# hm3_redraw.net
KiCad netlist of a schematic drawn in EAGLE
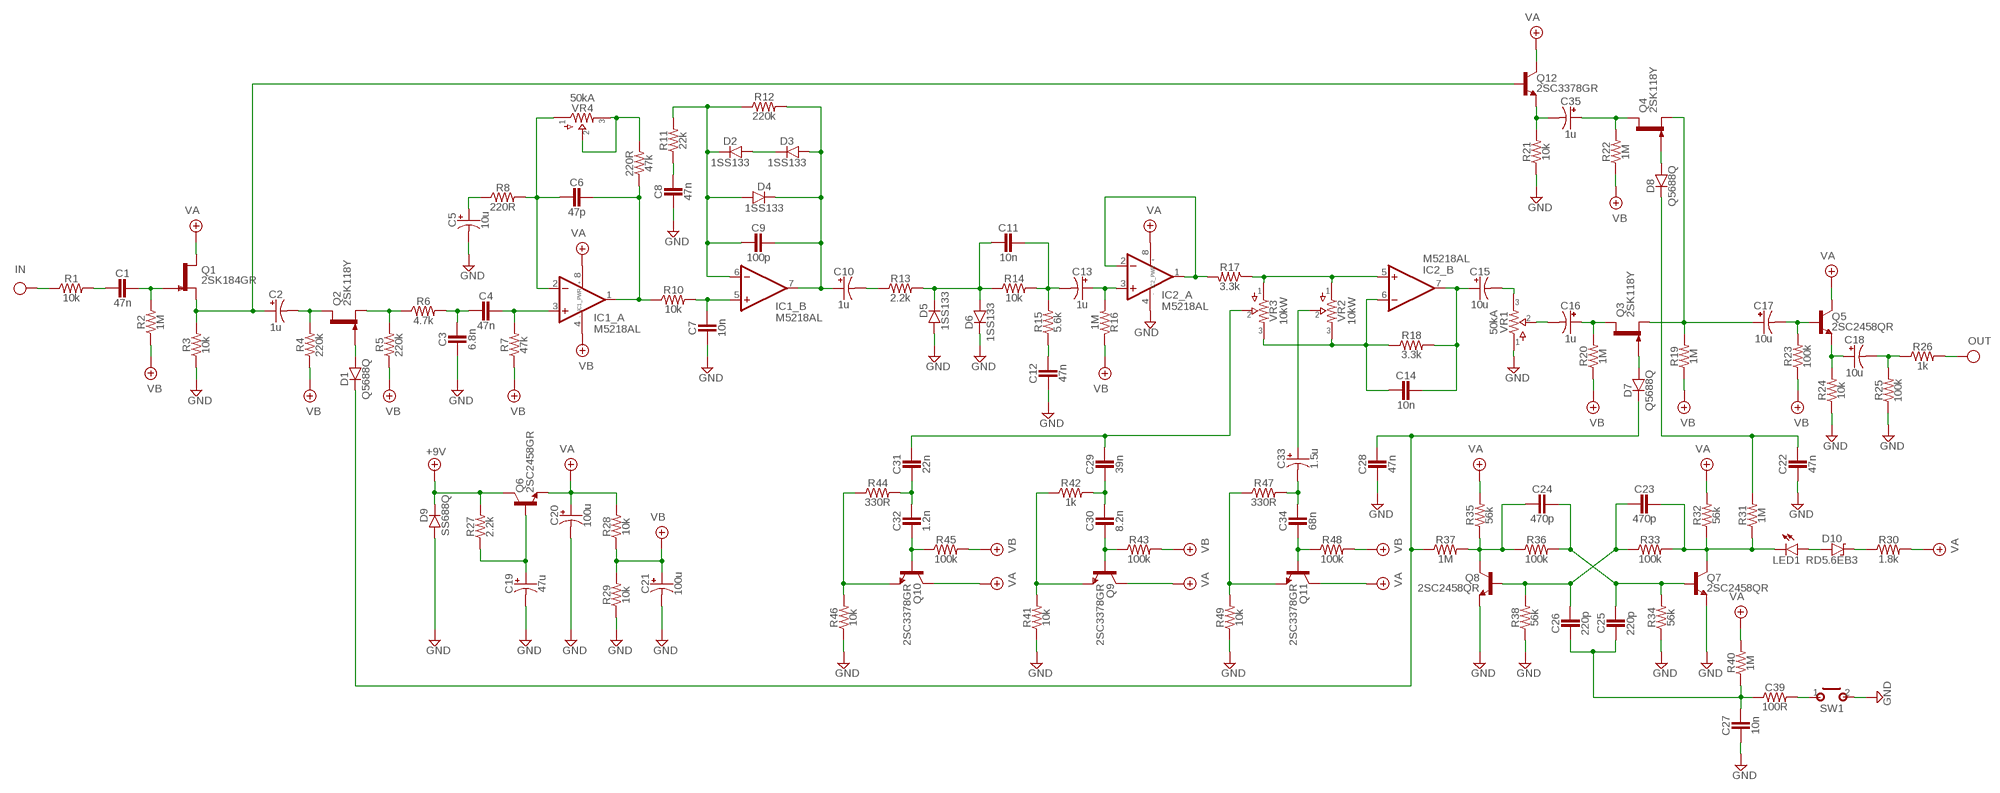
[diagram p0: schematic, sheet 1]

(export (version "E")
  (design (tool "Eeschema 10.0.6"))
  (components
    (comp (ref "220R")
      (value "47k")
      (footprint "eagle-import:R0207_3")
      (libsource (lib "eagle-import") (part "R_.3B"))
    )
    (comp (ref "C1")
      (value "47n")
      (footprint "eagle-import:BOX_SMALL")
      (libsource (lib "eagle-import") (part "CER/FILMBOX.1"))
    )
    (comp (ref "C2")
      (value "1u")
      (footprint "eagle-import:050_020")
      (libsource (lib "eagle-import") (part "0500"))
    )
    (comp (ref "C3")
      (value "6.8n")
      (footprint "eagle-import:BOX_SMALL")
      (libsource (lib "eagle-import") (part "CER/FILMBOX.1"))
    )
    (comp (ref "C4")
      (value "47n")
      (footprint "eagle-import:BOX_SMALL")
      (libsource (lib "eagle-import") (part "CER/FILMBOX.1"))
    )
    (comp (ref "C5")
      (value "10u")
      (footprint "eagle-import:050_020")
      (libsource (lib "eagle-import") (part "0500"))
    )
    (comp (ref "C6")
      (value "47p")
      (footprint "eagle-import:BOX_SMALL")
      (libsource (lib "eagle-import") (part "CER/FILMBOX.1"))
    )
    (comp (ref "C7")
      (value "10n")
      (footprint "eagle-import:BOX_SMALL")
      (libsource (lib "eagle-import") (part "CER/FILMBOX.1"))
    )
    (comp (ref "C8")
      (value "47n")
      (footprint "eagle-import:BOX_SMALL")
      (libsource (lib "eagle-import") (part "CER/FILMBOX.1"))
    )
    (comp (ref "C9")
      (value "100p")
      (footprint "eagle-import:BOX_SMALL")
      (libsource (lib "eagle-import") (part "CER/FILMBOX.1"))
    )
    (comp (ref "C10")
      (value "1u")
      (footprint "eagle-import:050_020")
      (libsource (lib "eagle-import") (part "0500"))
    )
    (comp (ref "C11")
      (value "10n")
      (footprint "eagle-import:BOX_SMALL")
      (libsource (lib "eagle-import") (part "CER/FILMBOX.1"))
    )
    (comp (ref "C12")
      (value "47n")
      (footprint "eagle-import:BOX_SMALL")
      (libsource (lib "eagle-import") (part "CER/FILMBOX.1"))
    )
    (comp (ref "C13")
      (value "1u")
      (footprint "eagle-import:050_020")
      (libsource (lib "eagle-import") (part "0500"))
    )
    (comp (ref "C14")
      (value "10n")
      (footprint "eagle-import:BOX_SMALL")
      (libsource (lib "eagle-import") (part "CER/FILMBOX.1"))
    )
    (comp (ref "C15")
      (value "10u")
      (footprint "eagle-import:050_020")
      (libsource (lib "eagle-import") (part "0500"))
    )
    (comp (ref "C16")
      (value "1u")
      (footprint "eagle-import:050_020")
      (libsource (lib "eagle-import") (part "0500"))
    )
    (comp (ref "C17")
      (value "10u")
      (footprint "eagle-import:050_020")
      (libsource (lib "eagle-import") (part "0500"))
    )
    (comp (ref "C18")
      (value "10u")
      (footprint "eagle-import:050_020")
      (libsource (lib "eagle-import") (part "0500"))
    )
    (comp (ref "C19")
      (value "47u")
      (footprint "eagle-import:050_020")
      (libsource (lib "eagle-import") (part "0500"))
    )
    (comp (ref "C20")
      (value "100u")
      (footprint "eagle-import:050_020")
      (libsource (lib "eagle-import") (part "0500"))
    )
    (comp (ref "C21")
      (value "100u")
      (footprint "eagle-import:050_020")
      (libsource (lib "eagle-import") (part "0500"))
    )
    (comp (ref "C22")
      (value "47n")
      (footprint "eagle-import:BOX_SMALL")
      (libsource (lib "eagle-import") (part "CER/FILMBOX.1"))
    )
    (comp (ref "C23")
      (value "470p")
      (footprint "eagle-import:BOX_SMALL")
      (libsource (lib "eagle-import") (part "CER/FILMBOX.1"))
    )
    (comp (ref "C24")
      (value "470p")
      (footprint "eagle-import:BOX_SMALL")
      (libsource (lib "eagle-import") (part "CER/FILMBOX.1"))
    )
    (comp (ref "C25")
      (value "220p")
      (footprint "eagle-import:BOX_SMALL")
      (libsource (lib "eagle-import") (part "CER/FILMBOX.1"))
    )
    (comp (ref "C26")
      (value "220p")
      (footprint "eagle-import:BOX_SMALL")
      (libsource (lib "eagle-import") (part "CER/FILMBOX.1"))
    )
    (comp (ref "C27")
      (value "10n")
      (footprint "eagle-import:BOX_SMALL")
      (libsource (lib "eagle-import") (part "CER/FILMBOX.1"))
    )
    (comp (ref "C28")
      (value "47n")
      (footprint "eagle-import:BOX_SMALL")
      (libsource (lib "eagle-import") (part "CER/FILMBOX.1"))
    )
    (comp (ref "C29")
      (value "39n")
      (footprint "eagle-import:BOX_SMALL")
      (libsource (lib "eagle-import") (part "CER/FILMBOX.1"))
    )
    (comp (ref "C30")
      (value "8.2n")
      (footprint "eagle-import:BOX_SMALL")
      (libsource (lib "eagle-import") (part "CER/FILMBOX.1"))
    )
    (comp (ref "C31")
      (value "22n")
      (footprint "eagle-import:BOX_SMALL")
      (libsource (lib "eagle-import") (part "CER/FILMBOX.1"))
    )
    (comp (ref "C32")
      (value "1.2n")
      (footprint "eagle-import:BOX_SMALL")
      (libsource (lib "eagle-import") (part "CER/FILMBOX.1"))
    )
    (comp (ref "C33")
      (value "1.5u")
      (footprint "eagle-import:050_020")
      (libsource (lib "eagle-import") (part "0500"))
    )
    (comp (ref "C34")
      (value "68n")
      (footprint "eagle-import:BOX_SMALL")
      (libsource (lib "eagle-import") (part "CER/FILMBOX.1"))
    )
    (comp (ref "C35")
      (value "1u")
      (footprint "eagle-import:050_020")
      (libsource (lib "eagle-import") (part "0500"))
    )
    (comp (ref "C39")
      (value "100R")
      (footprint "eagle-import:R0207_3")
      (libsource (lib "eagle-import") (part "R_.3B"))
    )
    (comp (ref "D1")
      (value "Q5688Q")
      (footprint "eagle-import:DO35-2")
      (libsource (lib "eagle-import") (part "DO35.2"))
    )
    (comp (ref "D2")
      (value "1SS133")
      (footprint "eagle-import:DO35-2")
      (libsource (lib "eagle-import") (part "DO35.2"))
    )
    (comp (ref "D3")
      (value "1SS133")
      (footprint "eagle-import:DO35-2")
      (libsource (lib "eagle-import") (part "DO35.2"))
    )
    (comp (ref "D4")
      (value "1SS133")
      (footprint "eagle-import:DO35-2")
      (libsource (lib "eagle-import") (part "DO35.2"))
    )
    (comp (ref "D5")
      (value "1SS133")
      (footprint "eagle-import:DO35-2")
      (libsource (lib "eagle-import") (part "DO35.2"))
    )
    (comp (ref "D6")
      (value "1SS133")
      (footprint "eagle-import:DO35-2")
      (libsource (lib "eagle-import") (part "DO35.2"))
    )
    (comp (ref "D7")
      (value "Q5688Q")
      (footprint "eagle-import:DO35-2")
      (libsource (lib "eagle-import") (part "DO35.2"))
    )
    (comp (ref "D8")
      (value "Q5688Q")
      (footprint "eagle-import:DO35-2")
      (libsource (lib "eagle-import") (part "DO35.2"))
    )
    (comp (ref "D9")
      (value "SS688Q")
      (footprint "eagle-import:DO35-2")
      (libsource (lib "eagle-import") (part "DO35.2"))
    )
    (comp (ref "D10")
      (value "RD5.6EB3")
      (footprint "eagle-import:DO41-2")
      (libsource (lib "eagle-import") (part "ZENER.2"))
    )
    (comp (ref "IC1")
      (value "M5218AL")
      (footprint "eagle-import:DIL0")
      (libsource (lib "eagle-import") (part "DUALTH"))
    )
    (comp (ref "IC2")
      (value "M5218AL")
      (footprint "eagle-import:SIL08")
      (libsource (lib "eagle-import") (part "DUALSIL"))
    )
    (comp (ref "LED1")
      (value "LED")
      (footprint "eagle-import:3MM_D")
      (libsource (lib "eagle-import") (part "LED"))
    )
    (comp (ref "Q1")
      (value "2SK184GR")
      (footprint "eagle-import:TO92-")
      (libsource (lib "eagle-import") (part "2N5457"))
    )
    (comp (ref "Q2")
      (value "2SK118Y")
      (footprint "eagle-import:TO92-")
      (libsource (lib "eagle-import") (part "2N5457"))
    )
    (comp (ref "Q3")
      (value "2SK118Y")
      (footprint "eagle-import:TO92-")
      (libsource (lib "eagle-import") (part "2N5457"))
    )
    (comp (ref "Q4")
      (value "2SK118Y")
      (footprint "eagle-import:TO92-")
      (libsource (lib "eagle-import") (part "2N5457"))
    )
    (comp (ref "Q5")
      (value "2SC2458QR")
      (footprint "eagle-import:TO92-")
      (libsource (lib "eagle-import") (part "2SC828A"))
    )
    (comp (ref "Q6")
      (value "2SC2458GR")
      (footprint "eagle-import:TO92-")
      (libsource (lib "eagle-import") (part "2SC828A"))
    )
    (comp (ref "Q7")
      (value "2SC2458QR")
      (footprint "eagle-import:TO92-")
      (libsource (lib "eagle-import") (part "2SC828A"))
    )
    (comp (ref "Q8")
      (value "2SC2458QR")
      (footprint "eagle-import:TO92-")
      (libsource (lib "eagle-import") (part "2SC828A"))
    )
    (comp (ref "Q9")
      (value "2SC3378GR")
      (footprint "eagle-import:TO92-")
      (libsource (lib "eagle-import") (part "2SC828A"))
    )
    (comp (ref "Q10")
      (value "2SC3378GR")
      (footprint "eagle-import:TO92-")
      (libsource (lib "eagle-import") (part "2SC828A"))
    )
    (comp (ref "Q11")
      (value "2SC3378GR")
      (footprint "eagle-import:TO92-")
      (libsource (lib "eagle-import") (part "2SC828A"))
    )
    (comp (ref "Q12")
      (value "2SC3378GR")
      (footprint "eagle-import:TO92-")
      (libsource (lib "eagle-import") (part "2SC828A"))
    )
    (comp (ref "R1")
      (value "10k")
      (footprint "eagle-import:R0207_3")
      (libsource (lib "eagle-import") (part "R_.3B"))
    )
    (comp (ref "R2")
      (value "1M")
      (footprint "eagle-import:R0207_3")
      (libsource (lib "eagle-import") (part "R_.3B"))
    )
    (comp (ref "R3")
      (value "10k")
      (footprint "eagle-import:R0207_3")
      (libsource (lib "eagle-import") (part "R_.3B"))
    )
    (comp (ref "R4")
      (value "220k")
      (footprint "eagle-import:R0207_3")
      (libsource (lib "eagle-import") (part "R_.3B"))
    )
    (comp (ref "R5")
      (value "220k")
      (footprint "eagle-import:R0207_3")
      (libsource (lib "eagle-import") (part "R_.3B"))
    )
    (comp (ref "R6")
      (value "4.7k")
      (footprint "eagle-import:R0207_3")
      (libsource (lib "eagle-import") (part "R_.3B"))
    )
    (comp (ref "R7")
      (value "47k")
      (footprint "eagle-import:R0207_3")
      (libsource (lib "eagle-import") (part "R_.3B"))
    )
    (comp (ref "R8")
      (value "220R")
      (footprint "eagle-import:R0207_3")
      (libsource (lib "eagle-import") (part "R_.3B"))
    )
    (comp (ref "R10")
      (value "10k")
      (footprint "eagle-import:R0207_3")
      (libsource (lib "eagle-import") (part "R_.3B"))
    )
    (comp (ref "R11")
      (value "22k")
      (footprint "eagle-import:R0207_3")
      (libsource (lib "eagle-import") (part "R_.3B"))
    )
    (comp (ref "R12")
      (value "220k")
      (footprint "eagle-import:R0207_3")
      (libsource (lib "eagle-import") (part "R_.3B"))
    )
    (comp (ref "R13")
      (value "2.2k")
      (footprint "eagle-import:R0207_3")
      (libsource (lib "eagle-import") (part "R_.3B"))
    )
    (comp (ref "R14")
      (value "10k")
      (footprint "eagle-import:R0207_3")
      (libsource (lib "eagle-import") (part "R_.3B"))
    )
    (comp (ref "R15")
      (value "5.6k")
      (footprint "eagle-import:R0207_3")
      (libsource (lib "eagle-import") (part "R_.3B"))
    )
    (comp (ref "R16")
      (value "1M")
      (footprint "eagle-import:R0207_3")
      (libsource (lib "eagle-import") (part "R_.3B"))
    )
    (comp (ref "R17")
      (value "3.3k")
      (footprint "eagle-import:R0207_3")
      (libsource (lib "eagle-import") (part "R_.3B"))
    )
    (comp (ref "R18")
      (value "3.3k")
      (footprint "eagle-import:R0207_3")
      (libsource (lib "eagle-import") (part "R_.3B"))
    )
    (comp (ref "R19")
      (value "1M")
      (footprint "eagle-import:R0207_3")
      (libsource (lib "eagle-import") (part "R_.3B"))
    )
    (comp (ref "R20")
      (value "1M")
      (footprint "eagle-import:R0207_3")
      (libsource (lib "eagle-import") (part "R_.3B"))
    )
    (comp (ref "R21")
      (value "10k")
      (footprint "eagle-import:R0207_3")
      (libsource (lib "eagle-import") (part "R_.3B"))
    )
    (comp (ref "R22")
      (value "1M")
      (footprint "eagle-import:R0207_3")
      (libsource (lib "eagle-import") (part "R_.3B"))
    )
    (comp (ref "R23")
      (value "100k")
      (footprint "eagle-import:R0207_3")
      (libsource (lib "eagle-import") (part "R_.3B"))
    )
    (comp (ref "R24")
      (value "10k")
      (footprint "eagle-import:R0207_3")
      (libsource (lib "eagle-import") (part "R_.3B"))
    )
    (comp (ref "R25")
      (value "100k")
      (footprint "eagle-import:R0207_3")
      (libsource (lib "eagle-import") (part "R_.3B"))
    )
    (comp (ref "R26")
      (value "1k")
      (footprint "eagle-import:R0207_3")
      (libsource (lib "eagle-import") (part "R_.3B"))
    )
    (comp (ref "R27")
      (value "2.2k")
      (footprint "eagle-import:R0207_3")
      (libsource (lib "eagle-import") (part "R_.3B"))
    )
    (comp (ref "R28")
      (value "10k")
      (footprint "eagle-import:R0207_3")
      (libsource (lib "eagle-import") (part "R_.3B"))
    )
    (comp (ref "R29")
      (value "10k")
      (footprint "eagle-import:R0207_3")
      (libsource (lib "eagle-import") (part "R_.3B"))
    )
    (comp (ref "R30")
      (value "1.8k")
      (footprint "eagle-import:R0207_3")
      (libsource (lib "eagle-import") (part "R_.3B"))
    )
    (comp (ref "R31")
      (value "1M")
      (footprint "eagle-import:R0207_3")
      (libsource (lib "eagle-import") (part "R_.3B"))
    )
    (comp (ref "R32")
      (value "56k")
      (footprint "eagle-import:R0207_3")
      (libsource (lib "eagle-import") (part "R_.3B"))
    )
    (comp (ref "R33")
      (value "100k")
      (footprint "eagle-import:R0207_3")
      (libsource (lib "eagle-import") (part "R_.3B"))
    )
    (comp (ref "R34")
      (value "56k")
      (footprint "eagle-import:R0207_3")
      (libsource (lib "eagle-import") (part "R_.3B"))
    )
    (comp (ref "R35")
      (value "56k")
      (footprint "eagle-import:R0207_3")
      (libsource (lib "eagle-import") (part "R_.3B"))
    )
    (comp (ref "R36")
      (value "100k")
      (footprint "eagle-import:R0207_3")
      (libsource (lib "eagle-import") (part "R_.3B"))
    )
    (comp (ref "R37")
      (value "1M")
      (footprint "eagle-import:R0207_3")
      (libsource (lib "eagle-import") (part "R_.3B"))
    )
    (comp (ref "R38")
      (value "56k")
      (footprint "eagle-import:R0207_3")
      (libsource (lib "eagle-import") (part "R_.3B"))
    )
    (comp (ref "R40")
      (value "1M")
      (footprint "eagle-import:R0207_3")
      (libsource (lib "eagle-import") (part "R_.3B"))
    )
    (comp (ref "R41")
      (value "10k")
      (footprint "eagle-import:R0207_3")
      (libsource (lib "eagle-import") (part "R_.3B"))
    )
    (comp (ref "R42")
      (value "1k")
      (footprint "eagle-import:R0207_3")
      (libsource (lib "eagle-import") (part "R_.3B"))
    )
    (comp (ref "R43")
      (value "100k")
      (footprint "eagle-import:R0207_3")
      (libsource (lib "eagle-import") (part "R_.3B"))
    )
    (comp (ref "R44")
      (value "330R")
      (footprint "eagle-import:R0207_3")
      (libsource (lib "eagle-import") (part "R_.3B"))
    )
    (comp (ref "R45")
      (value "100k")
      (footprint "eagle-import:R0207_3")
      (libsource (lib "eagle-import") (part "R_.3B"))
    )
    (comp (ref "R46")
      (value "10k")
      (footprint "eagle-import:R0207_3")
      (libsource (lib "eagle-import") (part "R_.3B"))
    )
    (comp (ref "R47")
      (value "330R")
      (footprint "eagle-import:R0207_3")
      (libsource (lib "eagle-import") (part "R_.3B"))
    )
    (comp (ref "R48")
      (value "100k")
      (footprint "eagle-import:R0207_3")
      (libsource (lib "eagle-import") (part "R_.3B"))
    )
    (comp (ref "R49")
      (value "10k")
      (footprint "eagle-import:R0207_3")
      (libsource (lib "eagle-import") (part "R_.3B"))
    )
    (comp (ref "SW1")
      (value "MOMENTARY")
      (footprint "eagle-import:SPST")
      (libsource (lib "eagle-import") (part "MOMENTARY"))
    )
    (comp (ref "VR1")
      (value "50kA")
      (footprint "eagle-import:16MM")
      (libsource (lib "eagle-import") (part "POTS16MM"))
    )
    (comp (ref "VR2")
      (value "10kW")
      (footprint "eagle-import:16MM")
      (libsource (lib "eagle-import") (part "POTS16MM"))
    )
    (comp (ref "VR3")
      (value "10kW")
      (footprint "eagle-import:16MM")
      (libsource (lib "eagle-import") (part "POTS16MM"))
    )
    (comp (ref "VR4")
      (value "50kA")
      (footprint "eagle-import:16MM")
      (libsource (lib "eagle-import") (part "POTS16MM"))
    )
  )
  (nets
    (net (code "1") (name "+9V") (class "Default")
      (node (ref "D9") (pin "C") (pinfunction "C_C") (pintype "passive"))
      (node (ref "Q6") (pin "2") (pinfunction "C_2") (pintype "passive"))
      (node (ref "R27") (pin "2") (pinfunction "2_2") (pintype "passive"))
    )
    (net (code "2") (name "GND") (class "Default")
      (node (ref "C12") (pin "2") (pinfunction "2_2") (pintype "passive"))
      (node (ref "C19") (pin "-") (pinfunction "-_-") (pintype "passive"))
      (node (ref "C20") (pin "-") (pinfunction "-_-") (pintype "passive"))
      (node (ref "C21") (pin "-") (pinfunction "-_-") (pintype "passive"))
      (node (ref "C22") (pin "2") (pinfunction "2_2") (pintype "passive"))
      (node (ref "C27") (pin "2") (pinfunction "2_2") (pintype "passive"))
      (node (ref "C28") (pin "2") (pinfunction "2_2") (pintype "passive"))
      (node (ref "C3") (pin "2") (pinfunction "2_2") (pintype "passive"))
      (node (ref "C5") (pin "-") (pinfunction "-_-") (pintype "passive"))
      (node (ref "C7") (pin "2") (pinfunction "2_2") (pintype "passive"))
      (node (ref "C8") (pin "2") (pinfunction "2_2") (pintype "passive"))
      (node (ref "D5") (pin "A") (pinfunction "A_A") (pintype "passive"))
      (node (ref "D6") (pin "C") (pinfunction "C_C") (pintype "passive"))
      (node (ref "D9") (pin "A") (pinfunction "A_A") (pintype "passive"))
      (node (ref "IC2") (pin "4") (pinfunction "V-_4") (pintype "power_in"))
      (node (ref "Q7") (pin "3") (pinfunction "E_3") (pintype "passive"))
      (node (ref "Q8") (pin "3") (pinfunction "E_3") (pintype "passive"))
      (node (ref "R21") (pin "1") (pinfunction "1_1") (pintype "passive"))
      (node (ref "R24") (pin "1") (pinfunction "1_1") (pintype "passive"))
      (node (ref "R25") (pin "1") (pinfunction "1_1") (pintype "passive"))
      (node (ref "R29") (pin "1") (pinfunction "1_1") (pintype "passive"))
      (node (ref "R3") (pin "1") (pinfunction "1_1") (pintype "passive"))
      (node (ref "R34") (pin "1") (pinfunction "1_1") (pintype "passive"))
      (node (ref "R38") (pin "1") (pinfunction "1_1") (pintype "passive"))
      (node (ref "R41") (pin "1") (pinfunction "1_1") (pintype "passive"))
      (node (ref "R46") (pin "1") (pinfunction "1_1") (pintype "passive"))
      (node (ref "R49") (pin "1") (pinfunction "1_1") (pintype "passive"))
      (node (ref "SW1") (pin "2") (pinfunction "S_2") (pintype "passive"))
      (node (ref "VR1") (pin "1") (pinfunction "1_1") (pintype "passive"))
    )
    (net (code "3") (name "IN") (class "Default")
      (node (ref "R1") (pin "1") (pinfunction "1_1") (pintype "passive"))
    )
    (net (code "4") (name "Net-(220R-Pad2)") (class "Default")
      (node (ref "220R") (pin "2") (pinfunction "2_2") (pintype "passive"))
      (node (ref "VR4") (pin "2") (pinfunction "2_2") (pintype "passive"))
      (node (ref "VR4") (pin "3") (pinfunction "3_3") (pintype "passive"))
    )
    (net (code "5") (name "Net-(C1-Pad2)") (class "Default")
      (node (ref "C1") (pin "2") (pinfunction "2_2") (pintype "passive"))
      (node (ref "R1") (pin "2") (pinfunction "2_2") (pintype "passive"))
    )
    (net (code "6") (name "Net-(C3-Pad1)") (class "Default")
      (node (ref "C3") (pin "1") (pinfunction "1_1") (pintype "passive"))
      (node (ref "C4") (pin "2") (pinfunction "2_2") (pintype "passive"))
      (node (ref "R6") (pin "2") (pinfunction "2_2") (pintype "passive"))
    )
    (net (code "7") (name "Net-(C5-Pad+)") (class "Default")
      (node (ref "C5") (pin "+") (pinfunction "+_+") (pintype "passive"))
      (node (ref "R8") (pin "1") (pinfunction "1_1") (pintype "passive"))
    )
    (net (code "8") (name "Net-(C8-Pad1)") (class "Default")
      (node (ref "C8") (pin "1") (pinfunction "1_1") (pintype "passive"))
      (node (ref "R11") (pin "1") (pinfunction "1_1") (pintype "passive"))
    )
    (net (code "9") (name "Net-(C10-Pad-)") (class "Default")
      (node (ref "C10") (pin "-") (pinfunction "-_-") (pintype "passive"))
      (node (ref "R13") (pin "1") (pinfunction "1_1") (pintype "passive"))
    )
    (net (code "10") (name "Net-(C11-Pad1)") (class "Default")
      (node (ref "C11") (pin "1") (pinfunction "1_1") (pintype "passive"))
      (node (ref "C13") (pin "-") (pinfunction "-_-") (pintype "passive"))
      (node (ref "R14") (pin "2") (pinfunction "2_2") (pintype "passive"))
      (node (ref "R15") (pin "2") (pinfunction "2_2") (pintype "passive"))
    )
    (net (code "11") (name "Net-(C11-Pad2)") (class "Default")
      (node (ref "C11") (pin "2") (pinfunction "2_2") (pintype "passive"))
      (node (ref "D5") (pin "C") (pinfunction "C_C") (pintype "passive"))
      (node (ref "D6") (pin "A") (pinfunction "A_A") (pintype "passive"))
      (node (ref "R13") (pin "2") (pinfunction "2_2") (pintype "passive"))
      (node (ref "R14") (pin "1") (pinfunction "1_1") (pintype "passive"))
    )
    (net (code "12") (name "Net-(C12-Pad1)") (class "Default")
      (node (ref "C12") (pin "1") (pinfunction "1_1") (pintype "passive"))
      (node (ref "R15") (pin "1") (pinfunction "1_1") (pintype "passive"))
    )
    (net (code "13") (name "Net-(C15-Pad-)") (class "Default")
      (node (ref "C15") (pin "-") (pinfunction "-_-") (pintype "passive"))
      (node (ref "VR1") (pin "3") (pinfunction "3_3") (pintype "passive"))
    )
    (net (code "14") (name "Net-(C16-Pad-)") (class "Default")
      (node (ref "C16") (pin "-") (pinfunction "-_-") (pintype "passive"))
      (node (ref "VR1") (pin "2") (pinfunction "2_2") (pintype "passive"))
    )
    (net (code "15") (name "Net-(C18-Pad-)") (class "Default")
      (node (ref "C18") (pin "-") (pinfunction "-_-") (pintype "passive"))
      (node (ref "R25") (pin "2") (pinfunction "2_2") (pintype "passive"))
      (node (ref "R26") (pin "1") (pinfunction "1_1") (pintype "passive"))
    )
    (net (code "16") (name "Net-(C22-Pad1)") (class "Default")
      (node (ref "C22") (pin "1") (pinfunction "1_1") (pintype "passive"))
      (node (ref "D8") (pin "C") (pinfunction "C_C") (pintype "passive"))
      (node (ref "R31") (pin "2") (pinfunction "2_2") (pintype "passive"))
    )
    (net (code "17") (name "Net-(C25-Pad2)") (class "Default")
      (node (ref "C25") (pin "2") (pinfunction "2_2") (pintype "passive"))
      (node (ref "C26") (pin "2") (pinfunction "2_2") (pintype "passive"))
      (node (ref "C27") (pin "1") (pinfunction "1_1") (pintype "passive"))
      (node (ref "C39") (pin "1") (pinfunction "1_1") (pintype "passive"))
      (node (ref "R40") (pin "1") (pinfunction "1_1") (pintype "passive"))
    )
    (net (code "18") (name "Net-(C28-Pad1)") (class "Default")
      (node (ref "C28") (pin "1") (pinfunction "1_1") (pintype "passive"))
      (node (ref "D1") (pin "C") (pinfunction "C_C") (pintype "passive"))
      (node (ref "D7") (pin "C") (pinfunction "C_C") (pintype "passive"))
      (node (ref "R37") (pin "1") (pinfunction "1_1") (pintype "passive"))
    )
    (net (code "19") (name "Net-(C29-Pad1)") (class "Default")
      (node (ref "C29") (pin "1") (pinfunction "1_1") (pintype "passive"))
      (node (ref "C31") (pin "1") (pinfunction "1_1") (pintype "passive"))
      (node (ref "VR3") (pin "2") (pinfunction "2_2") (pintype "passive"))
    )
    (net (code "20") (name "Net-(C29-Pad2)") (class "Default")
      (node (ref "C29") (pin "2") (pinfunction "2_2") (pintype "passive"))
      (node (ref "C30") (pin "1") (pinfunction "1_1") (pintype "passive"))
      (node (ref "R42") (pin "2") (pinfunction "2_2") (pintype "passive"))
    )
    (net (code "21") (name "Net-(C31-Pad2)") (class "Default")
      (node (ref "C31") (pin "2") (pinfunction "2_2") (pintype "passive"))
      (node (ref "C32") (pin "1") (pinfunction "1_1") (pintype "passive"))
      (node (ref "R44") (pin "2") (pinfunction "2_2") (pintype "passive"))
    )
    (net (code "22") (name "Net-(C33-Pad+)") (class "Default")
      (node (ref "C33") (pin "+") (pinfunction "+_+") (pintype "passive"))
      (node (ref "VR2") (pin "2") (pinfunction "2_2") (pintype "passive"))
    )
    (net (code "23") (name "Net-(C33-Pad-)") (class "Default")
      (node (ref "C33") (pin "-") (pinfunction "-_-") (pintype "passive"))
      (node (ref "C34") (pin "1") (pinfunction "1_1") (pintype "passive"))
      (node (ref "R47") (pin "2") (pinfunction "2_2") (pintype "passive"))
    )
    (net (code "24") (name "Net-(D2-PadA)") (class "Default")
      (node (ref "D2") (pin "A") (pinfunction "A_A") (pintype "passive"))
      (node (ref "D3") (pin "C") (pinfunction "C_C") (pintype "passive"))
    )
    (net (code "25") (name "Net-(D10-PadC)") (class "Default")
      (node (ref "D10") (pin "C") (pinfunction "C_C") (pintype "passive"))
      (node (ref "R30") (pin "1") (pinfunction "1_1") (pintype "passive"))
    )
    (net (code "26") (name "Net-(IC1A-+IN)") (class "Default")
      (node (ref "C4") (pin "1") (pinfunction "1_1") (pintype "passive"))
      (node (ref "IC1") (pin "3") (pinfunction "+IN_3") (pintype "input"))
      (node (ref "R7") (pin "2") (pinfunction "2_2") (pintype "passive"))
    )
    (net (code "27") (name "Net-(IC1A--IN)") (class "Default")
      (node (ref "C6") (pin "2") (pinfunction "2_2") (pintype "passive"))
      (node (ref "IC1") (pin "2") (pinfunction "-IN_2") (pintype "input"))
      (node (ref "R8") (pin "2") (pinfunction "2_2") (pintype "passive"))
      (node (ref "VR4") (pin "1") (pinfunction "1_1") (pintype "passive"))
    )
    (net (code "28") (name "Net-(IC1A-OUT)") (class "Default")
      (node (ref "220R") (pin "1") (pinfunction "1_1") (pintype "passive"))
      (node (ref "C6") (pin "1") (pinfunction "1_1") (pintype "passive"))
      (node (ref "IC1") (pin "1") (pinfunction "OUT_1") (pintype "output"))
      (node (ref "R10") (pin "1") (pinfunction "1_1") (pintype "passive"))
    )
    (net (code "29") (name "Net-(IC1B-+IN)") (class "Default")
      (node (ref "C7") (pin "1") (pinfunction "1_1") (pintype "passive"))
      (node (ref "IC1") (pin "5") (pinfunction "+IN_5") (pintype "input"))
      (node (ref "R10") (pin "2") (pinfunction "2_2") (pintype "passive"))
    )
    (net (code "30") (name "Net-(IC1B--IN)") (class "Default")
      (node (ref "C9") (pin "2") (pinfunction "2_2") (pintype "passive"))
      (node (ref "D2") (pin "C") (pinfunction "C_C") (pintype "passive"))
      (node (ref "D4") (pin "A") (pinfunction "A_A") (pintype "passive"))
      (node (ref "IC1") (pin "6") (pinfunction "-IN_6") (pintype "input"))
      (node (ref "R11") (pin "2") (pinfunction "2_2") (pintype "passive"))
      (node (ref "R12") (pin "1") (pinfunction "1_1") (pintype "passive"))
    )
    (net (code "31") (name "Net-(IC1B-OUT)") (class "Default")
      (node (ref "C10") (pin "+") (pinfunction "+_+") (pintype "passive"))
      (node (ref "C9") (pin "1") (pinfunction "1_1") (pintype "passive"))
      (node (ref "D3") (pin "A") (pinfunction "A_A") (pintype "passive"))
      (node (ref "D4") (pin "C") (pinfunction "C_C") (pintype "passive"))
      (node (ref "IC1") (pin "7") (pinfunction "OUT_7") (pintype "output"))
      (node (ref "R12") (pin "2") (pinfunction "2_2") (pintype "passive"))
    )
    (net (code "32") (name "Net-(IC2A-+IN)") (class "Default")
      (node (ref "C13") (pin "+") (pinfunction "+_+") (pintype "passive"))
      (node (ref "IC2") (pin "3") (pinfunction "+IN_3") (pintype "input"))
      (node (ref "R16") (pin "2") (pinfunction "2_2") (pintype "passive"))
    )
    (net (code "33") (name "Net-(IC2A--IN)") (class "Default")
      (node (ref "IC2") (pin "1") (pinfunction "OUT_1") (pintype "output"))
      (node (ref "IC2") (pin "2") (pinfunction "-IN_2") (pintype "input"))
      (node (ref "R17") (pin "2") (pinfunction "2_2") (pintype "passive"))
    )
    (net (code "34") (name "Net-(IC2B-+IN)") (class "Default")
      (node (ref "IC2") (pin "5") (pinfunction "+IN_5") (pintype "input"))
      (node (ref "R17") (pin "1") (pinfunction "1_1") (pintype "passive"))
      (node (ref "VR2") (pin "1") (pinfunction "1_1") (pintype "passive"))
      (node (ref "VR3") (pin "1") (pinfunction "1_1") (pintype "passive"))
    )
    (net (code "35") (name "Net-(IC2B--IN)") (class "Default")
      (node (ref "C14") (pin "2") (pinfunction "2_2") (pintype "passive"))
      (node (ref "IC2") (pin "6") (pinfunction "-IN_6") (pintype "input"))
      (node (ref "R18") (pin "1") (pinfunction "1_1") (pintype "passive"))
      (node (ref "VR2") (pin "3") (pinfunction "3_3") (pintype "passive"))
      (node (ref "VR3") (pin "3") (pinfunction "3_3") (pintype "passive"))
    )
    (net (code "36") (name "Net-(IC2B-OUT)") (class "Default")
      (node (ref "C14") (pin "1") (pinfunction "1_1") (pintype "passive"))
      (node (ref "C15") (pin "+") (pinfunction "+_+") (pintype "passive"))
      (node (ref "IC2") (pin "7") (pinfunction "OUT_7") (pintype "output"))
      (node (ref "R18") (pin "2") (pinfunction "2_2") (pintype "passive"))
    )
    (net (code "37") (name "Net-(LED1-A)") (class "Default")
      (node (ref "D10") (pin "A") (pinfunction "A_A") (pintype "passive"))
      (node (ref "LED1") (pin "ANODE") (pinfunction "A_ANODE") (pintype "passive"))
    )
    (net (code "38") (name "Net-(LED1-C)") (class "Default")
      (node (ref "C23") (pin "1") (pinfunction "1_1") (pintype "passive"))
      (node (ref "LED1") (pin "P$1") (pinfunction "C_P$1") (pintype "passive"))
      (node (ref "Q7") (pin "2") (pinfunction "C_2") (pintype "passive"))
      (node (ref "R31") (pin "1") (pinfunction "1_1") (pintype "passive"))
      (node (ref "R32") (pin "1") (pinfunction "1_1") (pintype "passive"))
      (node (ref "R33") (pin "2") (pinfunction "2_2") (pintype "passive"))
    )
    (net (code "39") (name "Net-(Q1-G)") (class "Default")
      (node (ref "C1") (pin "1") (pinfunction "1_1") (pintype "passive"))
      (node (ref "Q1") (pin "1") (pinfunction "G_1") (pintype "passive"))
      (node (ref "R2") (pin "2") (pinfunction "2_2") (pintype "passive"))
    )
    (net (code "40") (name "Net-(Q1-S)") (class "Default")
      (node (ref "C2") (pin "+") (pinfunction "+_+") (pintype "passive"))
      (node (ref "Q1") (pin "2") (pinfunction "S_2") (pintype "passive"))
      (node (ref "Q12") (pin "1") (pinfunction "B_1") (pintype "passive"))
      (node (ref "R3") (pin "2") (pinfunction "2_2") (pintype "passive"))
    )
    (net (code "41") (name "Net-(Q2-D)") (class "Default")
      (node (ref "C2") (pin "-") (pinfunction "-_-") (pintype "passive"))
      (node (ref "Q2") (pin "3") (pinfunction "D_3") (pintype "passive"))
      (node (ref "R4") (pin "2") (pinfunction "2_2") (pintype "passive"))
    )
    (net (code "42") (name "Net-(Q2-G)") (class "Default")
      (node (ref "D1") (pin "A") (pinfunction "A_A") (pintype "passive"))
      (node (ref "Q2") (pin "1") (pinfunction "G_1") (pintype "passive"))
    )
    (net (code "43") (name "Net-(Q2-S)") (class "Default")
      (node (ref "Q2") (pin "2") (pinfunction "S_2") (pintype "passive"))
      (node (ref "R5") (pin "2") (pinfunction "2_2") (pintype "passive"))
      (node (ref "R6") (pin "1") (pinfunction "1_1") (pintype "passive"))
    )
    (net (code "44") (name "Net-(Q3-D)") (class "Default")
      (node (ref "C16") (pin "+") (pinfunction "+_+") (pintype "passive"))
      (node (ref "Q3") (pin "3") (pinfunction "D_3") (pintype "passive"))
      (node (ref "R20") (pin "2") (pinfunction "2_2") (pintype "passive"))
    )
    (net (code "45") (name "Net-(Q3-G)") (class "Default")
      (node (ref "D7") (pin "A") (pinfunction "A_A") (pintype "passive"))
      (node (ref "Q3") (pin "1") (pinfunction "G_1") (pintype "passive"))
    )
    (net (code "46") (name "Net-(Q3-S)") (class "Default")
      (node (ref "C17") (pin "+") (pinfunction "+_+") (pintype "passive"))
      (node (ref "Q3") (pin "2") (pinfunction "S_2") (pintype "passive"))
      (node (ref "Q4") (pin "2") (pinfunction "S_2") (pintype "passive"))
      (node (ref "R19") (pin "2") (pinfunction "2_2") (pintype "passive"))
    )
    (net (code "47") (name "Net-(Q4-D)") (class "Default")
      (node (ref "C35") (pin "+") (pinfunction "+_+") (pintype "passive"))
      (node (ref "Q4") (pin "3") (pinfunction "D_3") (pintype "passive"))
      (node (ref "R22") (pin "2") (pinfunction "2_2") (pintype "passive"))
    )
    (net (code "48") (name "Net-(Q4-G)") (class "Default")
      (node (ref "D8") (pin "A") (pinfunction "A_A") (pintype "passive"))
      (node (ref "Q4") (pin "1") (pinfunction "G_1") (pintype "passive"))
    )
    (net (code "49") (name "Net-(Q5-B)") (class "Default")
      (node (ref "C17") (pin "-") (pinfunction "-_-") (pintype "passive"))
      (node (ref "Q5") (pin "1") (pinfunction "B_1") (pintype "passive"))
      (node (ref "R23") (pin "2") (pinfunction "2_2") (pintype "passive"))
    )
    (net (code "50") (name "Net-(Q5-E)") (class "Default")
      (node (ref "C18") (pin "+") (pinfunction "+_+") (pintype "passive"))
      (node (ref "Q5") (pin "3") (pinfunction "E_3") (pintype "passive"))
      (node (ref "R24") (pin "2") (pinfunction "2_2") (pintype "passive"))
    )
    (net (code "51") (name "Net-(Q6-B)") (class "Default")
      (node (ref "C19") (pin "+") (pinfunction "+_+") (pintype "passive"))
      (node (ref "Q6") (pin "1") (pinfunction "B_1") (pintype "passive"))
      (node (ref "R27") (pin "1") (pinfunction "1_1") (pintype "passive"))
    )
    (net (code "52") (name "Net-(Q7-B)") (class "Default")
      (node (ref "C24") (pin "1") (pinfunction "1_1") (pintype "passive"))
      (node (ref "C25") (pin "1") (pinfunction "1_1") (pintype "passive"))
      (node (ref "Q7") (pin "1") (pinfunction "B_1") (pintype "passive"))
      (node (ref "R34") (pin "2") (pinfunction "2_2") (pintype "passive"))
      (node (ref "R36") (pin "2") (pinfunction "2_2") (pintype "passive"))
    )
    (net (code "53") (name "Net-(Q8-B)") (class "Default")
      (node (ref "C23") (pin "2") (pinfunction "2_2") (pintype "passive"))
      (node (ref "C26") (pin "1") (pinfunction "1_1") (pintype "passive"))
      (node (ref "Q8") (pin "1") (pinfunction "B_1") (pintype "passive"))
      (node (ref "R33") (pin "1") (pinfunction "1_1") (pintype "passive"))
      (node (ref "R38") (pin "2") (pinfunction "2_2") (pintype "passive"))
    )
    (net (code "54") (name "Net-(Q8-C)") (class "Default")
      (node (ref "C24") (pin "2") (pinfunction "2_2") (pintype "passive"))
      (node (ref "Q8") (pin "2") (pinfunction "C_2") (pintype "passive"))
      (node (ref "R35") (pin "1") (pinfunction "1_1") (pintype "passive"))
      (node (ref "R36") (pin "1") (pinfunction "1_1") (pintype "passive"))
      (node (ref "R37") (pin "2") (pinfunction "2_2") (pintype "passive"))
    )
    (net (code "55") (name "Net-(Q9-B)") (class "Default")
      (node (ref "C30") (pin "2") (pinfunction "2_2") (pintype "passive"))
      (node (ref "Q9") (pin "1") (pinfunction "B_1") (pintype "passive"))
      (node (ref "R43") (pin "1") (pinfunction "1_1") (pintype "passive"))
    )
    (net (code "56") (name "Net-(Q9-E)") (class "Default")
      (node (ref "Q9") (pin "3") (pinfunction "E_3") (pintype "passive"))
      (node (ref "R41") (pin "2") (pinfunction "2_2") (pintype "passive"))
      (node (ref "R42") (pin "1") (pinfunction "1_1") (pintype "passive"))
    )
    (net (code "57") (name "Net-(Q10-B)") (class "Default")
      (node (ref "C32") (pin "2") (pinfunction "2_2") (pintype "passive"))
      (node (ref "Q10") (pin "1") (pinfunction "B_1") (pintype "passive"))
      (node (ref "R45") (pin "1") (pinfunction "1_1") (pintype "passive"))
    )
    (net (code "58") (name "Net-(Q10-E)") (class "Default")
      (node (ref "Q10") (pin "3") (pinfunction "E_3") (pintype "passive"))
      (node (ref "R44") (pin "1") (pinfunction "1_1") (pintype "passive"))
      (node (ref "R46") (pin "2") (pinfunction "2_2") (pintype "passive"))
    )
    (net (code "59") (name "Net-(Q11-B)") (class "Default")
      (node (ref "C34") (pin "2") (pinfunction "2_2") (pintype "passive"))
      (node (ref "Q11") (pin "1") (pinfunction "B_1") (pintype "passive"))
      (node (ref "R48") (pin "1") (pinfunction "1_1") (pintype "passive"))
    )
    (net (code "60") (name "Net-(Q11-E)") (class "Default")
      (node (ref "Q11") (pin "3") (pinfunction "E_3") (pintype "passive"))
      (node (ref "R47") (pin "1") (pinfunction "1_1") (pintype "passive"))
      (node (ref "R49") (pin "2") (pinfunction "2_2") (pintype "passive"))
    )
    (net (code "61") (name "Net-(Q12-E)") (class "Default")
      (node (ref "C35") (pin "-") (pinfunction "-_-") (pintype "passive"))
      (node (ref "Q12") (pin "3") (pinfunction "E_3") (pintype "passive"))
      (node (ref "R21") (pin "2") (pinfunction "2_2") (pintype "passive"))
    )
    (net (code "62") (name "Net-(SW1-P)") (class "Default")
      (node (ref "C39") (pin "2") (pinfunction "2_2") (pintype "passive"))
      (node (ref "SW1") (pin "1") (pinfunction "P_1") (pintype "passive"))
    )
    (net (code "63") (name "OUT") (class "Default")
      (node (ref "R26") (pin "2") (pinfunction "2_2") (pintype "passive"))
    )
    (net (code "64") (name "VA") (class "Default")
      (node (ref "C20") (pin "+") (pinfunction "+_+") (pintype "passive"))
      (node (ref "IC1") (pin "8") (pinfunction "V+_8") (pintype "power_in"))
      (node (ref "IC2") (pin "8") (pinfunction "V+_8") (pintype "power_in"))
      (node (ref "Q1") (pin "3") (pinfunction "D_3") (pintype "passive"))
      (node (ref "Q10") (pin "2") (pinfunction "C_2") (pintype "passive"))
      (node (ref "Q11") (pin "2") (pinfunction "C_2") (pintype "passive"))
      (node (ref "Q12") (pin "2") (pinfunction "C_2") (pintype "passive"))
      (node (ref "Q5") (pin "2") (pinfunction "C_2") (pintype "passive"))
      (node (ref "Q6") (pin "3") (pinfunction "E_3") (pintype "passive"))
      (node (ref "Q9") (pin "2") (pinfunction "C_2") (pintype "passive"))
      (node (ref "R28") (pin "2") (pinfunction "2_2") (pintype "passive"))
      (node (ref "R30") (pin "2") (pinfunction "2_2") (pintype "passive"))
      (node (ref "R32") (pin "2") (pinfunction "2_2") (pintype "passive"))
      (node (ref "R35") (pin "2") (pinfunction "2_2") (pintype "passive"))
      (node (ref "R40") (pin "2") (pinfunction "2_2") (pintype "passive"))
    )
    (net (code "65") (name "VB") (class "Default")
      (node (ref "C21") (pin "+") (pinfunction "+_+") (pintype "passive"))
      (node (ref "IC1") (pin "4") (pinfunction "V-_4") (pintype "power_in"))
      (node (ref "R16") (pin "1") (pinfunction "1_1") (pintype "passive"))
      (node (ref "R19") (pin "1") (pinfunction "1_1") (pintype "passive"))
      (node (ref "R2") (pin "1") (pinfunction "1_1") (pintype "passive"))
      (node (ref "R20") (pin "1") (pinfunction "1_1") (pintype "passive"))
      (node (ref "R22") (pin "1") (pinfunction "1_1") (pintype "passive"))
      (node (ref "R23") (pin "1") (pinfunction "1_1") (pintype "passive"))
      (node (ref "R28") (pin "1") (pinfunction "1_1") (pintype "passive"))
      (node (ref "R29") (pin "2") (pinfunction "2_2") (pintype "passive"))
      (node (ref "R4") (pin "1") (pinfunction "1_1") (pintype "passive"))
      (node (ref "R43") (pin "2") (pinfunction "2_2") (pintype "passive"))
      (node (ref "R45") (pin "2") (pinfunction "2_2") (pintype "passive"))
      (node (ref "R48") (pin "2") (pinfunction "2_2") (pintype "passive"))
      (node (ref "R5") (pin "1") (pinfunction "1_1") (pintype "passive"))
      (node (ref "R7") (pin "1") (pinfunction "1_1") (pintype "passive"))
    )
  )
)
